# 2_HV_MUX.net
KiCad netlist of a schematic drawn in Altium Designer
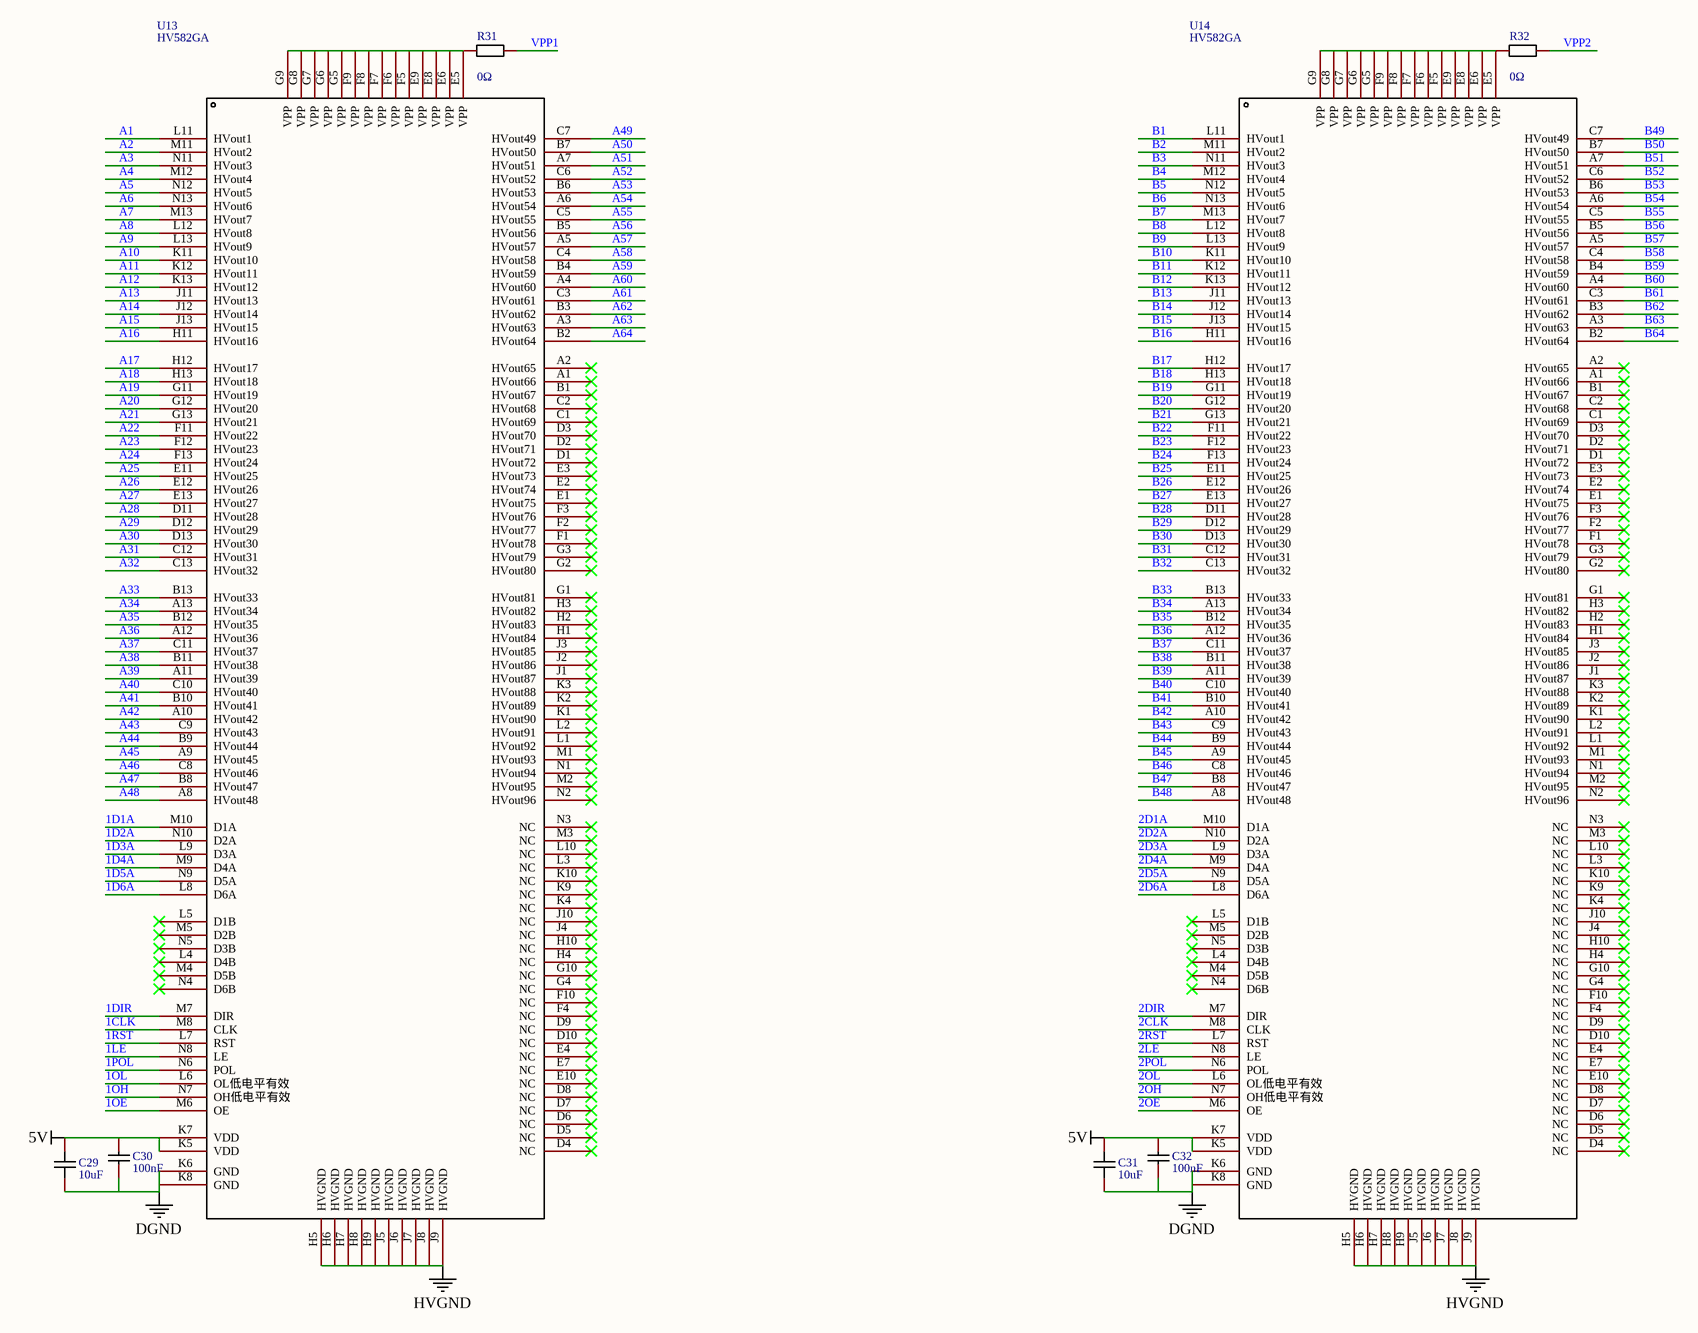
[diagram p0: 2_HV_MUX.schdoc]

(export (version "E")
  (design (tool "Eeschema 10.0.6"))
  (components
    (comp (ref "C29")
      (value "10uF")
      (fields
        (field (name "NAME") "10uF")
        (field (name "MANUFACTURER") "Samsung Electro-Mechanics")
        (field (name "MANUFACTURER PART") "CL05A106MP5NUNC")
      )
      (libsource (lib "altium-import") (part "root_1_CL05A106MP5NUNC_"))
    )
    (comp (ref "C30")
      (value "100nF")
      (fields
        (field (name "NAME") "100nF")
        (field (name "MANUFACTURER PART") "CL05B104KO5NNNC")
        (field (name "MANUFACTURER") "SAMSUNG")
      )
      (libsource (lib "altium-import") (part "root_1_CL05B104KO5NNNC_"))
    )
    (comp (ref "C31")
      (value "10uF")
      (fields
        (field (name "NAME") "10uF")
        (field (name "MANUFACTURER") "Samsung Electro-Mechanics")
        (field (name "MANUFACTURER PART") "CL05A106MP5NUNC")
      )
      (libsource (lib "altium-import") (part "root_1_CL05A106MP5NUNC_"))
    )
    (comp (ref "C32")
      (value "100nF")
      (fields
        (field (name "NAME") "100nF")
        (field (name "MANUFACTURER PART") "CL05B104KO5NNNC")
        (field (name "MANUFACTURER") "SAMSUNG")
      )
      (libsource (lib "altium-import") (part "root_1_CL05B104KO5NNNC_"))
    )
    (comp (ref "R31")
      (value "0Ω")
      (description "电阻类型:厚膜电阻;阻值:0Ω;精度:±1%;功率:250mW;温度系数:±800ppm/℃;最大工作电压:200V;工作温度范围:-55℃~+155℃;")
      (fields
        (field (name "MANUFACTURER") "UNI-ROYAL(厚声)")
        (field (name "MANUFACTURER PART") "1206W4F0000T5E")
      )
      (libsource (lib "altium-import") (part "root_0_1206W4F0000T5E_"))
    )
    (comp (ref "R32")
      (value "0Ω")
      (description "电阻类型:厚膜电阻;阻值:0Ω;精度:±1%;功率:250mW;温度系数:±800ppm/℃;最大工作电压:200V;工作温度范围:-55℃~+155℃;")
      (fields
        (field (name "MANUFACTURER") "UNI-ROYAL(厚声)")
        (field (name "MANUFACTURER PART") "1206W4F0000T5E")
      )
      (libsource (lib "altium-import") (part "root_0_1206W4F0000T5E_"))
    )
    (comp (ref "U13")
      (value "HV582GA")
      (fields (field (name "NAME") "HV582GA") (field (name "MANUFACTURER") "Microchip"))
      (libsource (lib "altium-import") (part "root_0_HV582GA_"))
    )
    (comp (ref "U14")
      (value "HV582GA")
      (fields (field (name "NAME") "HV582GA") (field (name "MANUFACTURER") "Microchip"))
      (libsource (lib "altium-import") (part "root_0_HV582GA_"))
    )
  )
  (nets
    (net (code "1") (name "/1CLK") (class "Default")
      (node (ref "U13") (pin "M8") (pinfunction "CLK_M8") (pintype "passive"))
    )
    (net (code "2") (name "/1D1A") (class "Default")
      (node (ref "U13") (pin "M10") (pinfunction "D1A_M10") (pintype "passive"))
    )
    (net (code "3") (name "/1D2A") (class "Default")
      (node (ref "U13") (pin "N10") (pinfunction "D2A_N10") (pintype "passive"))
    )
    (net (code "4") (name "/1D3A") (class "Default")
      (node (ref "U13") (pin "L9") (pinfunction "D3A_L9") (pintype "passive"))
    )
    (net (code "5") (name "/1D4A") (class "Default")
      (node (ref "U13") (pin "M9") (pinfunction "D4A_M9") (pintype "passive"))
    )
    (net (code "6") (name "/1D5A") (class "Default")
      (node (ref "U13") (pin "N9") (pinfunction "D5A_N9") (pintype "passive"))
    )
    (net (code "7") (name "/1D6A") (class "Default")
      (node (ref "U13") (pin "L8") (pinfunction "D6A_L8") (pintype "passive"))
    )
    (net (code "8") (name "/1DIR") (class "Default")
      (node (ref "U13") (pin "M7") (pinfunction "DIR_M7") (pintype "passive"))
    )
    (net (code "9") (name "/1LE") (class "Default")
      (node (ref "U13") (pin "N8") (pinfunction "LE_N8") (pintype "passive"))
    )
    (net (code "10") (name "/1OE") (class "Default")
      (node (ref "U13") (pin "M6") (pinfunction "OE_M6") (pintype "passive"))
    )
    (net (code "11") (name "/1OH") (class "Default")
      (node (ref "U13") (pin "N7") (pinfunction "OH低电平有效_N7") (pintype "passive"))
    )
    (net (code "12") (name "/1OL") (class "Default")
      (node (ref "U13") (pin "L6") (pinfunction "OL低电平有效_L6") (pintype "passive"))
    )
    (net (code "13") (name "/1POL") (class "Default")
      (node (ref "U13") (pin "N6") (pinfunction "POL_N6") (pintype "passive"))
    )
    (net (code "14") (name "/1RST") (class "Default")
      (node (ref "U13") (pin "L7") (pinfunction "RST_L7") (pintype "passive"))
    )
    (net (code "15") (name "/2CLK") (class "Default")
      (node (ref "U14") (pin "M8") (pinfunction "CLK_M8") (pintype "passive"))
    )
    (net (code "16") (name "/2D1A") (class "Default")
      (node (ref "U14") (pin "M10") (pinfunction "D1A_M10") (pintype "passive"))
    )
    (net (code "17") (name "/2D2A") (class "Default")
      (node (ref "U14") (pin "N10") (pinfunction "D2A_N10") (pintype "passive"))
    )
    (net (code "18") (name "/2D3A") (class "Default")
      (node (ref "U14") (pin "L9") (pinfunction "D3A_L9") (pintype "passive"))
    )
    (net (code "19") (name "/2D4A") (class "Default")
      (node (ref "U14") (pin "M9") (pinfunction "D4A_M9") (pintype "passive"))
    )
    (net (code "20") (name "/2D5A") (class "Default")
      (node (ref "U14") (pin "N9") (pinfunction "D5A_N9") (pintype "passive"))
    )
    (net (code "21") (name "/2D6A") (class "Default")
      (node (ref "U14") (pin "L8") (pinfunction "D6A_L8") (pintype "passive"))
    )
    (net (code "22") (name "/2DIR") (class "Default")
      (node (ref "U14") (pin "M7") (pinfunction "DIR_M7") (pintype "passive"))
    )
    (net (code "23") (name "/2LE") (class "Default")
      (node (ref "U14") (pin "N8") (pinfunction "LE_N8") (pintype "passive"))
    )
    (net (code "24") (name "/2OE") (class "Default")
      (node (ref "U14") (pin "M6") (pinfunction "OE_M6") (pintype "passive"))
    )
    (net (code "25") (name "/2OH") (class "Default")
      (node (ref "U14") (pin "N7") (pinfunction "OH低电平有效_N7") (pintype "passive"))
    )
    (net (code "26") (name "/2OL") (class "Default")
      (node (ref "U14") (pin "L6") (pinfunction "OL低电平有效_L6") (pintype "passive"))
    )
    (net (code "27") (name "/2POL") (class "Default")
      (node (ref "U14") (pin "N6") (pinfunction "POL_N6") (pintype "passive"))
    )
    (net (code "28") (name "/2RST") (class "Default")
      (node (ref "U14") (pin "L7") (pinfunction "RST_L7") (pintype "passive"))
    )
    (net (code "29") (name "/A1") (class "Default")
      (node (ref "U13") (pin "L11") (pinfunction "HVout1_L11") (pintype "passive"))
    )
    (net (code "30") (name "/A2") (class "Default")
      (node (ref "U13") (pin "M11") (pinfunction "HVout2_M11") (pintype "passive"))
    )
    (net (code "31") (name "/A3") (class "Default")
      (node (ref "U13") (pin "N11") (pinfunction "HVout3_N11") (pintype "passive"))
    )
    (net (code "32") (name "/A4") (class "Default")
      (node (ref "U13") (pin "M12") (pinfunction "HVout4_M12") (pintype "passive"))
    )
    (net (code "33") (name "/A5") (class "Default")
      (node (ref "U13") (pin "N12") (pinfunction "HVout5_N12") (pintype "passive"))
    )
    (net (code "34") (name "/A6") (class "Default")
      (node (ref "U13") (pin "N13") (pinfunction "HVout6_N13") (pintype "passive"))
    )
    (net (code "35") (name "/A7") (class "Default")
      (node (ref "U13") (pin "M13") (pinfunction "HVout7_M13") (pintype "passive"))
    )
    (net (code "36") (name "/A8") (class "Default")
      (node (ref "U13") (pin "L12") (pinfunction "HVout8_L12") (pintype "passive"))
    )
    (net (code "37") (name "/A9") (class "Default")
      (node (ref "U13") (pin "L13") (pinfunction "HVout9_L13") (pintype "passive"))
    )
    (net (code "38") (name "/A10") (class "Default")
      (node (ref "U13") (pin "K11") (pinfunction "HVout10_K11") (pintype "passive"))
    )
    (net (code "39") (name "/A11") (class "Default")
      (node (ref "U13") (pin "K12") (pinfunction "HVout11_K12") (pintype "passive"))
    )
    (net (code "40") (name "/A12") (class "Default")
      (node (ref "U13") (pin "K13") (pinfunction "HVout12_K13") (pintype "passive"))
    )
    (net (code "41") (name "/A13") (class "Default")
      (node (ref "U13") (pin "J11") (pinfunction "HVout13_J11") (pintype "passive"))
    )
    (net (code "42") (name "/A14") (class "Default")
      (node (ref "U13") (pin "J12") (pinfunction "HVout14_J12") (pintype "passive"))
    )
    (net (code "43") (name "/A15") (class "Default")
      (node (ref "U13") (pin "J13") (pinfunction "HVout15_J13") (pintype "passive"))
    )
    (net (code "44") (name "/A16") (class "Default")
      (node (ref "U13") (pin "H11") (pinfunction "HVout16_H11") (pintype "passive"))
    )
    (net (code "45") (name "/A17") (class "Default")
      (node (ref "U13") (pin "H12") (pinfunction "HVout17_H12") (pintype "passive"))
    )
    (net (code "46") (name "/A18") (class "Default")
      (node (ref "U13") (pin "H13") (pinfunction "HVout18_H13") (pintype "passive"))
    )
    (net (code "47") (name "/A19") (class "Default")
      (node (ref "U13") (pin "G11") (pinfunction "HVout19_G11") (pintype "passive"))
    )
    (net (code "48") (name "/A20") (class "Default")
      (node (ref "U13") (pin "G12") (pinfunction "HVout20_G12") (pintype "passive"))
    )
    (net (code "49") (name "/A21") (class "Default")
      (node (ref "U13") (pin "G13") (pinfunction "HVout21_G13") (pintype "passive"))
    )
    (net (code "50") (name "/A22") (class "Default")
      (node (ref "U13") (pin "F11") (pinfunction "HVout22_F11") (pintype "passive"))
    )
    (net (code "51") (name "/A23") (class "Default")
      (node (ref "U13") (pin "F12") (pinfunction "HVout23_F12") (pintype "passive"))
    )
    (net (code "52") (name "/A24") (class "Default")
      (node (ref "U13") (pin "F13") (pinfunction "HVout24_F13") (pintype "passive"))
    )
    (net (code "53") (name "/A25") (class "Default")
      (node (ref "U13") (pin "E11") (pinfunction "HVout25_E11") (pintype "passive"))
    )
    (net (code "54") (name "/A26") (class "Default")
      (node (ref "U13") (pin "E12") (pinfunction "HVout26_E12") (pintype "passive"))
    )
    (net (code "55") (name "/A27") (class "Default")
      (node (ref "U13") (pin "E13") (pinfunction "HVout27_E13") (pintype "passive"))
    )
    (net (code "56") (name "/A28") (class "Default")
      (node (ref "U13") (pin "D11") (pinfunction "HVout28_D11") (pintype "passive"))
    )
    (net (code "57") (name "/A29") (class "Default")
      (node (ref "U13") (pin "D12") (pinfunction "HVout29_D12") (pintype "passive"))
    )
    (net (code "58") (name "/A30") (class "Default")
      (node (ref "U13") (pin "D13") (pinfunction "HVout30_D13") (pintype "passive"))
    )
    (net (code "59") (name "/A31") (class "Default")
      (node (ref "U13") (pin "C12") (pinfunction "HVout31_C12") (pintype "passive"))
    )
    (net (code "60") (name "/A32") (class "Default")
      (node (ref "U13") (pin "C13") (pinfunction "HVout32_C13") (pintype "passive"))
    )
    (net (code "61") (name "/A33") (class "Default")
      (node (ref "U13") (pin "B13") (pinfunction "HVout33_B13") (pintype "passive"))
    )
    (net (code "62") (name "/A34") (class "Default")
      (node (ref "U13") (pin "A13") (pinfunction "HVout34_A13") (pintype "passive"))
    )
    (net (code "63") (name "/A35") (class "Default")
      (node (ref "U13") (pin "B12") (pinfunction "HVout35_B12") (pintype "passive"))
    )
    (net (code "64") (name "/A36") (class "Default")
      (node (ref "U13") (pin "A12") (pinfunction "HVout36_A12") (pintype "passive"))
    )
    (net (code "65") (name "/A37") (class "Default")
      (node (ref "U13") (pin "C11") (pinfunction "HVout37_C11") (pintype "passive"))
    )
    (net (code "66") (name "/A38") (class "Default")
      (node (ref "U13") (pin "B11") (pinfunction "HVout38_B11") (pintype "passive"))
    )
    (net (code "67") (name "/A39") (class "Default")
      (node (ref "U13") (pin "A11") (pinfunction "HVout39_A11") (pintype "passive"))
    )
    (net (code "68") (name "/A40") (class "Default")
      (node (ref "U13") (pin "C10") (pinfunction "HVout40_C10") (pintype "passive"))
    )
    (net (code "69") (name "/A41") (class "Default")
      (node (ref "U13") (pin "B10") (pinfunction "HVout41_B10") (pintype "passive"))
    )
    (net (code "70") (name "/A42") (class "Default")
      (node (ref "U13") (pin "A10") (pinfunction "HVout42_A10") (pintype "passive"))
    )
    (net (code "71") (name "/A43") (class "Default")
      (node (ref "U13") (pin "C9") (pinfunction "HVout43_C9") (pintype "passive"))
    )
    (net (code "72") (name "/A44") (class "Default")
      (node (ref "U13") (pin "B9") (pinfunction "HVout44_B9") (pintype "passive"))
    )
    (net (code "73") (name "/A45") (class "Default")
      (node (ref "U13") (pin "A9") (pinfunction "HVout45_A9") (pintype "passive"))
    )
    (net (code "74") (name "/A46") (class "Default")
      (node (ref "U13") (pin "C8") (pinfunction "HVout46_C8") (pintype "passive"))
    )
    (net (code "75") (name "/A47") (class "Default")
      (node (ref "U13") (pin "B8") (pinfunction "HVout47_B8") (pintype "passive"))
    )
    (net (code "76") (name "/A48") (class "Default")
      (node (ref "U13") (pin "A8") (pinfunction "HVout48_A8") (pintype "passive"))
    )
    (net (code "77") (name "/A49") (class "Default")
      (node (ref "U13") (pin "C7") (pinfunction "HVout49_C7") (pintype "passive"))
    )
    (net (code "78") (name "/A50") (class "Default")
      (node (ref "U13") (pin "B7") (pinfunction "HVout50_B7") (pintype "passive"))
    )
    (net (code "79") (name "/A51") (class "Default")
      (node (ref "U13") (pin "A7") (pinfunction "HVout51_A7") (pintype "passive"))
    )
    (net (code "80") (name "/A52") (class "Default")
      (node (ref "U13") (pin "C6") (pinfunction "HVout52_C6") (pintype "passive"))
    )
    (net (code "81") (name "/A53") (class "Default")
      (node (ref "U13") (pin "B6") (pinfunction "HVout53_B6") (pintype "passive"))
    )
    (net (code "82") (name "/A54") (class "Default")
      (node (ref "U13") (pin "A6") (pinfunction "HVout54_A6") (pintype "passive"))
    )
    (net (code "83") (name "/A55") (class "Default")
      (node (ref "U13") (pin "C5") (pinfunction "HVout55_C5") (pintype "passive"))
    )
    (net (code "84") (name "/A56") (class "Default")
      (node (ref "U13") (pin "B5") (pinfunction "HVout56_B5") (pintype "passive"))
    )
    (net (code "85") (name "/A57") (class "Default")
      (node (ref "U13") (pin "A5") (pinfunction "HVout57_A5") (pintype "passive"))
    )
    (net (code "86") (name "/A58") (class "Default")
      (node (ref "U13") (pin "C4") (pinfunction "HVout58_C4") (pintype "passive"))
    )
    (net (code "87") (name "/A59") (class "Default")
      (node (ref "U13") (pin "B4") (pinfunction "HVout59_B4") (pintype "passive"))
    )
    (net (code "88") (name "/A60") (class "Default")
      (node (ref "U13") (pin "A4") (pinfunction "HVout60_A4") (pintype "passive"))
    )
    (net (code "89") (name "/A61") (class "Default")
      (node (ref "U13") (pin "C3") (pinfunction "HVout61_C3") (pintype "passive"))
    )
    (net (code "90") (name "/A62") (class "Default")
      (node (ref "U13") (pin "B3") (pinfunction "HVout62_B3") (pintype "passive"))
    )
    (net (code "91") (name "/A63") (class "Default")
      (node (ref "U13") (pin "A3") (pinfunction "HVout63_A3") (pintype "passive"))
    )
    (net (code "92") (name "/A64") (class "Default")
      (node (ref "U13") (pin "B2") (pinfunction "HVout64_B2") (pintype "passive"))
    )
    (net (code "93") (name "/B1") (class "Default")
      (node (ref "U14") (pin "L11") (pinfunction "HVout1_L11") (pintype "passive"))
    )
    (net (code "94") (name "/B2") (class "Default")
      (node (ref "U14") (pin "M11") (pinfunction "HVout2_M11") (pintype "passive"))
    )
    (net (code "95") (name "/B3") (class "Default")
      (node (ref "U14") (pin "N11") (pinfunction "HVout3_N11") (pintype "passive"))
    )
    (net (code "96") (name "/B4") (class "Default")
      (node (ref "U14") (pin "M12") (pinfunction "HVout4_M12") (pintype "passive"))
    )
    (net (code "97") (name "/B5") (class "Default")
      (node (ref "U14") (pin "N12") (pinfunction "HVout5_N12") (pintype "passive"))
    )
    (net (code "98") (name "/B6") (class "Default")
      (node (ref "U14") (pin "N13") (pinfunction "HVout6_N13") (pintype "passive"))
    )
    (net (code "99") (name "/B7") (class "Default")
      (node (ref "U14") (pin "M13") (pinfunction "HVout7_M13") (pintype "passive"))
    )
    (net (code "100") (name "/B8") (class "Default")
      (node (ref "U14") (pin "L12") (pinfunction "HVout8_L12") (pintype "passive"))
    )
    (net (code "101") (name "/B9") (class "Default")
      (node (ref "U14") (pin "L13") (pinfunction "HVout9_L13") (pintype "passive"))
    )
    (net (code "102") (name "/B10") (class "Default")
      (node (ref "U14") (pin "K11") (pinfunction "HVout10_K11") (pintype "passive"))
    )
    (net (code "103") (name "/B11") (class "Default")
      (node (ref "U14") (pin "K12") (pinfunction "HVout11_K12") (pintype "passive"))
    )
    (net (code "104") (name "/B12") (class "Default")
      (node (ref "U14") (pin "K13") (pinfunction "HVout12_K13") (pintype "passive"))
    )
    (net (code "105") (name "/B13") (class "Default")
      (node (ref "U14") (pin "J11") (pinfunction "HVout13_J11") (pintype "passive"))
    )
    (net (code "106") (name "/B14") (class "Default")
      (node (ref "U14") (pin "J12") (pinfunction "HVout14_J12") (pintype "passive"))
    )
    (net (code "107") (name "/B15") (class "Default")
      (node (ref "U14") (pin "J13") (pinfunction "HVout15_J13") (pintype "passive"))
    )
    (net (code "108") (name "/B16") (class "Default")
      (node (ref "U14") (pin "H11") (pinfunction "HVout16_H11") (pintype "passive"))
    )
    (net (code "109") (name "/B17") (class "Default")
      (node (ref "U14") (pin "H12") (pinfunction "HVout17_H12") (pintype "passive"))
    )
    (net (code "110") (name "/B18") (class "Default")
      (node (ref "U14") (pin "H13") (pinfunction "HVout18_H13") (pintype "passive"))
    )
    (net (code "111") (name "/B19") (class "Default")
      (node (ref "U14") (pin "G11") (pinfunction "HVout19_G11") (pintype "passive"))
    )
    (net (code "112") (name "/B20") (class "Default")
      (node (ref "U14") (pin "G12") (pinfunction "HVout20_G12") (pintype "passive"))
    )
    (net (code "113") (name "/B21") (class "Default")
      (node (ref "U14") (pin "G13") (pinfunction "HVout21_G13") (pintype "passive"))
    )
    (net (code "114") (name "/B22") (class "Default")
      (node (ref "U14") (pin "F11") (pinfunction "HVout22_F11") (pintype "passive"))
    )
    (net (code "115") (name "/B23") (class "Default")
      (node (ref "U14") (pin "F12") (pinfunction "HVout23_F12") (pintype "passive"))
    )
    (net (code "116") (name "/B24") (class "Default")
      (node (ref "U14") (pin "F13") (pinfunction "HVout24_F13") (pintype "passive"))
    )
    (net (code "117") (name "/B25") (class "Default")
      (node (ref "U14") (pin "E11") (pinfunction "HVout25_E11") (pintype "passive"))
    )
    (net (code "118") (name "/B26") (class "Default")
      (node (ref "U14") (pin "E12") (pinfunction "HVout26_E12") (pintype "passive"))
    )
    (net (code "119") (name "/B27") (class "Default")
      (node (ref "U14") (pin "E13") (pinfunction "HVout27_E13") (pintype "passive"))
    )
    (net (code "120") (name "/B28") (class "Default")
      (node (ref "U14") (pin "D11") (pinfunction "HVout28_D11") (pintype "passive"))
    )
    (net (code "121") (name "/B29") (class "Default")
      (node (ref "U14") (pin "D12") (pinfunction "HVout29_D12") (pintype "passive"))
    )
    (net (code "122") (name "/B30") (class "Default")
      (node (ref "U14") (pin "D13") (pinfunction "HVout30_D13") (pintype "passive"))
    )
    (net (code "123") (name "/B31") (class "Default")
      (node (ref "U14") (pin "C12") (pinfunction "HVout31_C12") (pintype "passive"))
    )
    (net (code "124") (name "/B32") (class "Default")
      (node (ref "U14") (pin "C13") (pinfunction "HVout32_C13") (pintype "passive"))
    )
    (net (code "125") (name "/B33") (class "Default")
      (node (ref "U14") (pin "B13") (pinfunction "HVout33_B13") (pintype "passive"))
    )
    (net (code "126") (name "/B34") (class "Default")
      (node (ref "U14") (pin "A13") (pinfunction "HVout34_A13") (pintype "passive"))
    )
    (net (code "127") (name "/B35") (class "Default")
      (node (ref "U14") (pin "B12") (pinfunction "HVout35_B12") (pintype "passive"))
    )
    (net (code "128") (name "/B36") (class "Default")
      (node (ref "U14") (pin "A12") (pinfunction "HVout36_A12") (pintype "passive"))
    )
    (net (code "129") (name "/B37") (class "Default")
      (node (ref "U14") (pin "C11") (pinfunction "HVout37_C11") (pintype "passive"))
    )
    (net (code "130") (name "/B38") (class "Default")
      (node (ref "U14") (pin "B11") (pinfunction "HVout38_B11") (pintype "passive"))
    )
    (net (code "131") (name "/B39") (class "Default")
      (node (ref "U14") (pin "A11") (pinfunction "HVout39_A11") (pintype "passive"))
    )
    (net (code "132") (name "/B40") (class "Default")
      (node (ref "U14") (pin "C10") (pinfunction "HVout40_C10") (pintype "passive"))
    )
    (net (code "133") (name "/B41") (class "Default")
      (node (ref "U14") (pin "B10") (pinfunction "HVout41_B10") (pintype "passive"))
    )
    (net (code "134") (name "/B42") (class "Default")
      (node (ref "U14") (pin "A10") (pinfunction "HVout42_A10") (pintype "passive"))
    )
    (net (code "135") (name "/B43") (class "Default")
      (node (ref "U14") (pin "C9") (pinfunction "HVout43_C9") (pintype "passive"))
    )
    (net (code "136") (name "/B44") (class "Default")
      (node (ref "U14") (pin "B9") (pinfunction "HVout44_B9") (pintype "passive"))
    )
    (net (code "137") (name "/B45") (class "Default")
      (node (ref "U14") (pin "A9") (pinfunction "HVout45_A9") (pintype "passive"))
    )
    (net (code "138") (name "/B46") (class "Default")
      (node (ref "U14") (pin "C8") (pinfunction "HVout46_C8") (pintype "passive"))
    )
    (net (code "139") (name "/B47") (class "Default")
      (node (ref "U14") (pin "B8") (pinfunction "HVout47_B8") (pintype "passive"))
    )
    (net (code "140") (name "/B48") (class "Default")
      (node (ref "U14") (pin "A8") (pinfunction "HVout48_A8") (pintype "passive"))
    )
    (net (code "141") (name "/B49") (class "Default")
      (node (ref "U14") (pin "C7") (pinfunction "HVout49_C7") (pintype "passive"))
    )
    (net (code "142") (name "/B50") (class "Default")
      (node (ref "U14") (pin "B7") (pinfunction "HVout50_B7") (pintype "passive"))
    )
    (net (code "143") (name "/B51") (class "Default")
      (node (ref "U14") (pin "A7") (pinfunction "HVout51_A7") (pintype "passive"))
    )
    (net (code "144") (name "/B52") (class "Default")
      (node (ref "U14") (pin "C6") (pinfunction "HVout52_C6") (pintype "passive"))
    )
    (net (code "145") (name "/B53") (class "Default")
      (node (ref "U14") (pin "B6") (pinfunction "HVout53_B6") (pintype "passive"))
    )
    (net (code "146") (name "/B54") (class "Default")
      (node (ref "U14") (pin "A6") (pinfunction "HVout54_A6") (pintype "passive"))
    )
    (net (code "147") (name "/B55") (class "Default")
      (node (ref "U14") (pin "C5") (pinfunction "HVout55_C5") (pintype "passive"))
    )
    (net (code "148") (name "/B56") (class "Default")
      (node (ref "U14") (pin "B5") (pinfunction "HVout56_B5") (pintype "passive"))
    )
    (net (code "149") (name "/B57") (class "Default")
      (node (ref "U14") (pin "A5") (pinfunction "HVout57_A5") (pintype "passive"))
    )
    (net (code "150") (name "/B58") (class "Default")
      (node (ref "U14") (pin "C4") (pinfunction "HVout58_C4") (pintype "passive"))
    )
    (net (code "151") (name "/B59") (class "Default")
      (node (ref "U14") (pin "B4") (pinfunction "HVout59_B4") (pintype "passive"))
    )
    (net (code "152") (name "/B60") (class "Default")
      (node (ref "U14") (pin "A4") (pinfunction "HVout60_A4") (pintype "passive"))
    )
    (net (code "153") (name "/B61") (class "Default")
      (node (ref "U14") (pin "C3") (pinfunction "HVout61_C3") (pintype "passive"))
    )
    (net (code "154") (name "/B62") (class "Default")
      (node (ref "U14") (pin "B3") (pinfunction "HVout62_B3") (pintype "passive"))
    )
    (net (code "155") (name "/B63") (class "Default")
      (node (ref "U14") (pin "A3") (pinfunction "HVout63_A3") (pintype "passive"))
    )
    (net (code "156") (name "/B64") (class "Default")
      (node (ref "U14") (pin "B2") (pinfunction "HVout64_B2") (pintype "passive"))
    )
    (net (code "157") (name "/VPP1") (class "Default")
      (node (ref "R31") (pin "2") (pinfunction "2_2") (pintype "passive"))
    )
    (net (code "158") (name "/VPP2") (class "Default")
      (node (ref "R32") (pin "2") (pinfunction "2_2") (pintype "passive"))
    )
    (net (code "159") (name "5V") (class "Default")
      (node (ref "C29") (pin "2") (pinfunction "2_2") (pintype "passive"))
      (node (ref "C30") (pin "2") (pinfunction "2_2") (pintype "passive"))
      (node (ref "C31") (pin "2") (pinfunction "2_2") (pintype "passive"))
      (node (ref "C32") (pin "2") (pinfunction "2_2") (pintype "passive"))
      (node (ref "U13") (pin "K5") (pinfunction "VDD_K5") (pintype "passive"))
      (node (ref "U13") (pin "K7") (pinfunction "VDD_K7") (pintype "passive"))
      (node (ref "U14") (pin "K5") (pinfunction "VDD_K5") (pintype "passive"))
      (node (ref "U14") (pin "K7") (pinfunction "VDD_K7") (pintype "passive"))
    )
    (net (code "160") (name "DGND") (class "Default")
      (node (ref "C29") (pin "1") (pinfunction "1_1") (pintype "passive"))
      (node (ref "C30") (pin "1") (pinfunction "1_1") (pintype "passive"))
      (node (ref "C31") (pin "1") (pinfunction "1_1") (pintype "passive"))
      (node (ref "C32") (pin "1") (pinfunction "1_1") (pintype "passive"))
      (node (ref "U13") (pin "K6") (pinfunction "GND_K6") (pintype "passive"))
      (node (ref "U13") (pin "K8") (pinfunction "GND_K8") (pintype "passive"))
      (node (ref "U14") (pin "K6") (pinfunction "GND_K6") (pintype "passive"))
      (node (ref "U14") (pin "K8") (pinfunction "GND_K8") (pintype "passive"))
    )
    (net (code "161") (name "HVGND") (class "Default")
      (node (ref "U13") (pin "H5") (pinfunction "HVGND_H5") (pintype "passive"))
      (node (ref "U13") (pin "H6") (pinfunction "HVGND_H6") (pintype "passive"))
      (node (ref "U13") (pin "H7") (pinfunction "HVGND_H7") (pintype "passive"))
      (node (ref "U13") (pin "H8") (pinfunction "HVGND_H8") (pintype "passive"))
      (node (ref "U13") (pin "H9") (pinfunction "HVGND_H9") (pintype "passive"))
      (node (ref "U13") (pin "J5") (pinfunction "HVGND_J5") (pintype "passive"))
      (node (ref "U13") (pin "J6") (pinfunction "HVGND_J6") (pintype "passive"))
      (node (ref "U13") (pin "J7") (pinfunction "HVGND_J7") (pintype "passive"))
      (node (ref "U13") (pin "J8") (pinfunction "HVGND_J8") (pintype "passive"))
      (node (ref "U13") (pin "J9") (pinfunction "HVGND_J9") (pintype "passive"))
      (node (ref "U14") (pin "H5") (pinfunction "HVGND_H5") (pintype "passive"))
      (node (ref "U14") (pin "H6") (pinfunction "HVGND_H6") (pintype "passive"))
      (node (ref "U14") (pin "H7") (pinfunction "HVGND_H7") (pintype "passive"))
      (node (ref "U14") (pin "H8") (pinfunction "HVGND_H8") (pintype "passive"))
      (node (ref "U14") (pin "H9") (pinfunction "HVGND_H9") (pintype "passive"))
      (node (ref "U14") (pin "J5") (pinfunction "HVGND_J5") (pintype "passive"))
      (node (ref "U14") (pin "J6") (pinfunction "HVGND_J6") (pintype "passive"))
      (node (ref "U14") (pin "J7") (pinfunction "HVGND_J7") (pintype "passive"))
      (node (ref "U14") (pin "J8") (pinfunction "HVGND_J8") (pintype "passive"))
      (node (ref "U14") (pin "J9") (pinfunction "HVGND_J9") (pintype "passive"))
    )
    (net (code "162") (name "Net-(R31-Pad1)") (class "Default")
      (node (ref "R31") (pin "1") (pinfunction "1_1") (pintype "passive"))
      (node (ref "U13") (pin "E5") (pinfunction "VPP_E5") (pintype "passive"))
      (node (ref "U13") (pin "E6") (pinfunction "VPP_E6") (pintype "passive"))
      (node (ref "U13") (pin "E8") (pinfunction "VPP_E8") (pintype "passive"))
      (node (ref "U13") (pin "E9") (pinfunction "VPP_E9") (pintype "passive"))
      (node (ref "U13") (pin "F5") (pinfunction "VPP_F5") (pintype "passive"))
      (node (ref "U13") (pin "F6") (pinfunction "VPP_F6") (pintype "passive"))
      (node (ref "U13") (pin "F7") (pinfunction "VPP_F7") (pintype "passive"))
      (node (ref "U13") (pin "F8") (pinfunction "VPP_F8") (pintype "passive"))
      (node (ref "U13") (pin "F9") (pinfunction "VPP_F9") (pintype "passive"))
      (node (ref "U13") (pin "G5") (pinfunction "VPP_G5") (pintype "passive"))
      (node (ref "U13") (pin "G6") (pinfunction "VPP_G6") (pintype "passive"))
      (node (ref "U13") (pin "G7") (pinfunction "VPP_G7") (pintype "passive"))
      (node (ref "U13") (pin "G8") (pinfunction "VPP_G8") (pintype "passive"))
      (node (ref "U13") (pin "G9") (pinfunction "VPP_G9") (pintype "passive"))
    )
    (net (code "163") (name "Net-(R32-Pad1)") (class "Default")
      (node (ref "R32") (pin "1") (pinfunction "1_1") (pintype "passive"))
      (node (ref "U14") (pin "E5") (pinfunction "VPP_E5") (pintype "passive"))
      (node (ref "U14") (pin "E6") (pinfunction "VPP_E6") (pintype "passive"))
      (node (ref "U14") (pin "E8") (pinfunction "VPP_E8") (pintype "passive"))
      (node (ref "U14") (pin "E9") (pinfunction "VPP_E9") (pintype "passive"))
      (node (ref "U14") (pin "F5") (pinfunction "VPP_F5") (pintype "passive"))
      (node (ref "U14") (pin "F6") (pinfunction "VPP_F6") (pintype "passive"))
      (node (ref "U14") (pin "F7") (pinfunction "VPP_F7") (pintype "passive"))
      (node (ref "U14") (pin "F8") (pinfunction "VPP_F8") (pintype "passive"))
      (node (ref "U14") (pin "F9") (pinfunction "VPP_F9") (pintype "passive"))
      (node (ref "U14") (pin "G5") (pinfunction "VPP_G5") (pintype "passive"))
      (node (ref "U14") (pin "G6") (pinfunction "VPP_G6") (pintype "passive"))
      (node (ref "U14") (pin "G7") (pinfunction "VPP_G7") (pintype "passive"))
      (node (ref "U14") (pin "G8") (pinfunction "VPP_G8") (pintype "passive"))
      (node (ref "U14") (pin "G9") (pinfunction "VPP_G9") (pintype "passive"))
    )
    (net (code "164") (name "unconnected-(U13-D1B-PadL5)") (class "Default")
      (node (ref "U13") (pin "L5") (pinfunction "D1B_L5") (pintype "passive+no_connect"))
    )
    (net (code "165") (name "unconnected-(U13-D2B-PadM5)") (class "Default")
      (node (ref "U13") (pin "M5") (pinfunction "D2B_M5") (pintype "passive+no_connect"))
    )
    (net (code "166") (name "unconnected-(U13-D3B-PadN5)") (class "Default")
      (node (ref "U13") (pin "N5") (pinfunction "D3B_N5") (pintype "passive+no_connect"))
    )
    (net (code "167") (name "unconnected-(U13-D4B-PadL4)") (class "Default")
      (node (ref "U13") (pin "L4") (pinfunction "D4B_L4") (pintype "passive+no_connect"))
    )
    (net (code "168") (name "unconnected-(U13-D5B-PadM4)") (class "Default")
      (node (ref "U13") (pin "M4") (pinfunction "D5B_M4") (pintype "passive+no_connect"))
    )
    (net (code "169") (name "unconnected-(U13-D6B-PadN4)") (class "Default")
      (node (ref "U13") (pin "N4") (pinfunction "D6B_N4") (pintype "passive+no_connect"))
    )
    (net (code "170") (name "unconnected-(U13-HVout65-PadA2)") (class "Default")
      (node (ref "U13") (pin "A2") (pinfunction "HVout65_A2") (pintype "passive+no_connect"))
    )
    (net (code "171") (name "unconnected-(U13-HVout66-PadA1)") (class "Default")
      (node (ref "U13") (pin "A1") (pinfunction "HVout66_A1") (pintype "passive+no_connect"))
    )
    (net (code "172") (name "unconnected-(U13-HVout67-PadB1)") (class "Default")
      (node (ref "U13") (pin "B1") (pinfunction "HVout67_B1") (pintype "passive+no_connect"))
    )
    (net (code "173") (name "unconnected-(U13-HVout68-PadC2)") (class "Default")
      (node (ref "U13") (pin "C2") (pinfunction "HVout68_C2") (pintype "passive+no_connect"))
    )
    (net (code "174") (name "unconnected-(U13-HVout69-PadC1)") (class "Default")
      (node (ref "U13") (pin "C1") (pinfunction "HVout69_C1") (pintype "passive+no_connect"))
    )
    (net (code "175") (name "unconnected-(U13-HVout70-PadD3)") (class "Default")
      (node (ref "U13") (pin "D3") (pinfunction "HVout70_D3") (pintype "passive+no_connect"))
    )
    (net (code "176") (name "unconnected-(U13-HVout71-PadD2)") (class "Default")
      (node (ref "U13") (pin "D2") (pinfunction "HVout71_D2") (pintype "passive+no_connect"))
    )
    (net (code "177") (name "unconnected-(U13-HVout72-PadD1)") (class "Default")
      (node (ref "U13") (pin "D1") (pinfunction "HVout72_D1") (pintype "passive+no_connect"))
    )
    (net (code "178") (name "unconnected-(U13-HVout73-PadE3)") (class "Default")
      (node (ref "U13") (pin "E3") (pinfunction "HVout73_E3") (pintype "passive+no_connect"))
    )
    (net (code "179") (name "unconnected-(U13-HVout74-PadE2)") (class "Default")
      (node (ref "U13") (pin "E2") (pinfunction "HVout74_E2") (pintype "passive+no_connect"))
    )
    (net (code "180") (name "unconnected-(U13-HVout75-PadE1)") (class "Default")
      (node (ref "U13") (pin "E1") (pinfunction "HVout75_E1") (pintype "passive+no_connect"))
    )
    (net (code "181") (name "unconnected-(U13-HVout76-PadF3)") (class "Default")
      (node (ref "U13") (pin "F3") (pinfunction "HVout76_F3") (pintype "passive+no_connect"))
    )
    (net (code "182") (name "unconnected-(U13-HVout77-PadF2)") (class "Default")
      (node (ref "U13") (pin "F2") (pinfunction "HVout77_F2") (pintype "passive+no_connect"))
    )
    (net (code "183") (name "unconnected-(U13-HVout78-PadF1)") (class "Default")
      (node (ref "U13") (pin "F1") (pinfunction "HVout78_F1") (pintype "passive+no_connect"))
    )
    (net (code "184") (name "unconnected-(U13-HVout79-PadG3)") (class "Default")
      (node (ref "U13") (pin "G3") (pinfunction "HVout79_G3") (pintype "passive+no_connect"))
    )
    (net (code "185") (name "unconnected-(U13-HVout80-PadG2)") (class "Default")
      (node (ref "U13") (pin "G2") (pinfunction "HVout80_G2") (pintype "passive+no_connect"))
    )
    (net (code "186") (name "unconnected-(U13-HVout81-PadG1)") (class "Default")
      (node (ref "U13") (pin "G1") (pinfunction "HVout81_G1") (pintype "passive+no_connect"))
    )
    (net (code "187") (name "unconnected-(U13-HVout82-PadH3)") (class "Default")
      (node (ref "U13") (pin "H3") (pinfunction "HVout82_H3") (pintype "passive+no_connect"))
    )
    (net (code "188") (name "unconnected-(U13-HVout83-PadH2)") (class "Default")
      (node (ref "U13") (pin "H2") (pinfunction "HVout83_H2") (pintype "passive+no_connect"))
    )
    (net (code "189") (name "unconnected-(U13-HVout84-PadH1)") (class "Default")
      (node (ref "U13") (pin "H1") (pinfunction "HVout84_H1") (pintype "passive+no_connect"))
    )
    (net (code "190") (name "unconnected-(U13-HVout85-PadJ3)") (class "Default")
      (node (ref "U13") (pin "J3") (pinfunction "HVout85_J3") (pintype "passive+no_connect"))
    )
    (net (code "191") (name "unconnected-(U13-HVout86-PadJ2)") (class "Default")
      (node (ref "U13") (pin "J2") (pinfunction "HVout86_J2") (pintype "passive+no_connect"))
    )
    (net (code "192") (name "unconnected-(U13-HVout87-PadJ1)") (class "Default")
      (node (ref "U13") (pin "J1") (pinfunction "HVout87_J1") (pintype "passive+no_connect"))
    )
    (net (code "193") (name "unconnected-(U13-HVout88-PadK3)") (class "Default")
      (node (ref "U13") (pin "K3") (pinfunction "HVout88_K3") (pintype "passive+no_connect"))
    )
    (net (code "194") (name "unconnected-(U13-HVout89-PadK2)") (class "Default")
      (node (ref "U13") (pin "K2") (pinfunction "HVout89_K2") (pintype "passive+no_connect"))
    )
    (net (code "195") (name "unconnected-(U13-HVout90-PadK1)") (class "Default")
      (node (ref "U13") (pin "K1") (pinfunction "HVout90_K1") (pintype "passive+no_connect"))
    )
    (net (code "196") (name "unconnected-(U13-HVout91-PadL2)") (class "Default")
      (node (ref "U13") (pin "L2") (pinfunction "HVout91_L2") (pintype "passive+no_connect"))
    )
    (net (code "197") (name "unconnected-(U13-HVout92-PadL1)") (class "Default")
      (node (ref "U13") (pin "L1") (pinfunction "HVout92_L1") (pintype "passive+no_connect"))
    )
    (net (code "198") (name "unconnected-(U13-HVout93-PadM1)") (class "Default")
      (node (ref "U13") (pin "M1") (pinfunction "HVout93_M1") (pintype "passive+no_connect"))
    )
    (net (code "199") (name "unconnected-(U13-HVout94-PadN1)") (class "Default")
      (node (ref "U13") (pin "N1") (pinfunction "HVout94_N1") (pintype "passive+no_connect"))
    )
    (net (code "200") (name "unconnected-(U13-HVout95-PadM2)") (class "Default")
      (node (ref "U13") (pin "M2") (pinfunction "HVout95_M2") (pintype "passive+no_connect"))
    )
    (net (code "201") (name "unconnected-(U13-HVout96-PadN2)") (class "Default")
      (node (ref "U13") (pin "N2") (pinfunction "HVout96_N2") (pintype "passive+no_connect"))
    )
    (net (code "202") (name "unconnected-(U13-NC-PadD4)") (class "Default")
      (node (ref "U13") (pin "D4") (pinfunction "NC_D4") (pintype "passive+no_connect"))
    )
    (net (code "203") (name "unconnected-(U13-NC-PadD5)") (class "Default")
      (node (ref "U13") (pin "D5") (pinfunction "NC_D5") (pintype "passive+no_connect"))
    )
    (net (code "204") (name "unconnected-(U13-NC-PadD6)") (class "Default")
      (node (ref "U13") (pin "D6") (pinfunction "NC_D6") (pintype "passive+no_connect"))
    )
    (net (code "205") (name "unconnected-(U13-NC-PadD7)") (class "Default")
      (node (ref "U13") (pin "D7") (pinfunction "NC_D7") (pintype "passive+no_connect"))
    )
    (net (code "206") (name "unconnected-(U13-NC-PadD8)") (class "Default")
      (node (ref "U13") (pin "D8") (pinfunction "NC_D8") (pintype "passive+no_connect"))
    )
    (net (code "207") (name "unconnected-(U13-NC-PadD9)") (class "Default")
      (node (ref "U13") (pin "D9") (pinfunction "NC_D9") (pintype "passive+no_connect"))
    )
    (net (code "208") (name "unconnected-(U13-NC-PadD10)") (class "Default")
      (node (ref "U13") (pin "D10") (pinfunction "NC_D10") (pintype "passive+no_connect"))
    )
    (net (code "209") (name "unconnected-(U13-NC-PadE4)") (class "Default")
      (node (ref "U13") (pin "E4") (pinfunction "NC_E4") (pintype "passive+no_connect"))
    )
    (net (code "210") (name "unconnected-(U13-NC-PadE7)") (class "Default")
      (node (ref "U13") (pin "E7") (pinfunction "NC_E7") (pintype "passive+no_connect"))
    )
    (net (code "211") (name "unconnected-(U13-NC-PadE10)") (class "Default")
      (node (ref "U13") (pin "E10") (pinfunction "NC_E10") (pintype "passive+no_connect"))
    )
    (net (code "212") (name "unconnected-(U13-NC-PadF4)") (class "Default")
      (node (ref "U13") (pin "F4") (pinfunction "NC_F4") (pintype "passive+no_connect"))
    )
    (net (code "213") (name "unconnected-(U13-NC-PadF10)") (class "Default")
      (node (ref "U13") (pin "F10") (pinfunction "NC_F10") (pintype "passive+no_connect"))
    )
    (net (code "214") (name "unconnected-(U13-NC-PadG4)") (class "Default")
      (node (ref "U13") (pin "G4") (pinfunction "NC_G4") (pintype "passive+no_connect"))
    )
    (net (code "215") (name "unconnected-(U13-NC-PadG10)") (class "Default")
      (node (ref "U13") (pin "G10") (pinfunction "NC_G10") (pintype "passive+no_connect"))
    )
    (net (code "216") (name "unconnected-(U13-NC-PadH4)") (class "Default")
      (node (ref "U13") (pin "H4") (pinfunction "NC_H4") (pintype "passive+no_connect"))
    )
    (net (code "217") (name "unconnected-(U13-NC-PadH10)") (class "Default")
      (node (ref "U13") (pin "H10") (pinfunction "NC_H10") (pintype "passive+no_connect"))
    )
    (net (code "218") (name "unconnected-(U13-NC-PadJ4)") (class "Default")
      (node (ref "U13") (pin "J4") (pinfunction "NC_J4") (pintype "passive+no_connect"))
    )
    (net (code "219") (name "unconnected-(U13-NC-PadJ10)") (class "Default")
      (node (ref "U13") (pin "J10") (pinfunction "NC_J10") (pintype "passive+no_connect"))
    )
    (net (code "220") (name "unconnected-(U13-NC-PadK4)") (class "Default")
      (node (ref "U13") (pin "K4") (pinfunction "NC_K4") (pintype "passive+no_connect"))
    )
    (net (code "221") (name "unconnected-(U13-NC-PadK9)") (class "Default")
      (node (ref "U13") (pin "K9") (pinfunction "NC_K9") (pintype "passive+no_connect"))
    )
    (net (code "222") (name "unconnected-(U13-NC-PadK10)") (class "Default")
      (node (ref "U13") (pin "K10") (pinfunction "NC_K10") (pintype "passive+no_connect"))
    )
    (net (code "223") (name "unconnected-(U13-NC-PadL3)") (class "Default")
      (node (ref "U13") (pin "L3") (pinfunction "NC_L3") (pintype "passive+no_connect"))
    )
    (net (code "224") (name "unconnected-(U13-NC-PadL10)") (class "Default")
      (node (ref "U13") (pin "L10") (pinfunction "NC_L10") (pintype "passive+no_connect"))
    )
    (net (code "225") (name "unconnected-(U13-NC-PadM3)") (class "Default")
      (node (ref "U13") (pin "M3") (pinfunction "NC_M3") (pintype "passive+no_connect"))
    )
    (net (code "226") (name "unconnected-(U13-NC-PadN3)") (class "Default")
      (node (ref "U13") (pin "N3") (pinfunction "NC_N3") (pintype "passive+no_connect"))
    )
    (net (code "227") (name "unconnected-(U14-D1B-PadL5)") (class "Default")
      (node (ref "U14") (pin "L5") (pinfunction "D1B_L5") (pintype "passive+no_connect"))
    )
    (net (code "228") (name "unconnected-(U14-D2B-PadM5)") (class "Default")
      (node (ref "U14") (pin "M5") (pinfunction "D2B_M5") (pintype "passive+no_connect"))
    )
    (net (code "229") (name "unconnected-(U14-D3B-PadN5)") (class "Default")
      (node (ref "U14") (pin "N5") (pinfunction "D3B_N5") (pintype "passive+no_connect"))
    )
    (net (code "230") (name "unconnected-(U14-D4B-PadL4)") (class "Default")
      (node (ref "U14") (pin "L4") (pinfunction "D4B_L4") (pintype "passive+no_connect"))
    )
    (net (code "231") (name "unconnected-(U14-D5B-PadM4)") (class "Default")
      (node (ref "U14") (pin "M4") (pinfunction "D5B_M4") (pintype "passive+no_connect"))
    )
    (net (code "232") (name "unconnected-(U14-D6B-PadN4)") (class "Default")
      (node (ref "U14") (pin "N4") (pinfunction "D6B_N4") (pintype "passive+no_connect"))
    )
    (net (code "233") (name "unconnected-(U14-HVout65-PadA2)") (class "Default")
      (node (ref "U14") (pin "A2") (pinfunction "HVout65_A2") (pintype "passive+no_connect"))
    )
    (net (code "234") (name "unconnected-(U14-HVout66-PadA1)") (class "Default")
      (node (ref "U14") (pin "A1") (pinfunction "HVout66_A1") (pintype "passive+no_connect"))
    )
    (net (code "235") (name "unconnected-(U14-HVout67-PadB1)") (class "Default")
      (node (ref "U14") (pin "B1") (pinfunction "HVout67_B1") (pintype "passive+no_connect"))
    )
    (net (code "236") (name "unconnected-(U14-HVout68-PadC2)") (class "Default")
      (node (ref "U14") (pin "C2") (pinfunction "HVout68_C2") (pintype "passive+no_connect"))
    )
    (net (code "237") (name "unconnected-(U14-HVout69-PadC1)") (class "Default")
      (node (ref "U14") (pin "C1") (pinfunction "HVout69_C1") (pintype "passive+no_connect"))
    )
    (net (code "238") (name "unconnected-(U14-HVout70-PadD3)") (class "Default")
      (node (ref "U14") (pin "D3") (pinfunction "HVout70_D3") (pintype "passive+no_connect"))
    )
    (net (code "239") (name "unconnected-(U14-HVout71-PadD2)") (class "Default")
      (node (ref "U14") (pin "D2") (pinfunction "HVout71_D2") (pintype "passive+no_connect"))
    )
    (net (code "240") (name "unconnected-(U14-HVout72-PadD1)") (class "Default")
      (node (ref "U14") (pin "D1") (pinfunction "HVout72_D1") (pintype "passive+no_connect"))
    )
    (net (code "241") (name "unconnected-(U14-HVout73-PadE3)") (class "Default")
      (node (ref "U14") (pin "E3") (pinfunction "HVout73_E3") (pintype "passive+no_connect"))
    )
    (net (code "242") (name "unconnected-(U14-HVout74-PadE2)") (class "Default")
      (node (ref "U14") (pin "E2") (pinfunction "HVout74_E2") (pintype "passive+no_connect"))
    )
    (net (code "243") (name "unconnected-(U14-HVout75-PadE1)") (class "Default")
      (node (ref "U14") (pin "E1") (pinfunction "HVout75_E1") (pintype "passive+no_connect"))
    )
    (net (code "244") (name "unconnected-(U14-HVout76-PadF3)") (class "Default")
      (node (ref "U14") (pin "F3") (pinfunction "HVout76_F3") (pintype "passive+no_connect"))
    )
    (net (code "245") (name "unconnected-(U14-HVout77-PadF2)") (class "Default")
      (node (ref "U14") (pin "F2") (pinfunction "HVout77_F2") (pintype "passive+no_connect"))
    )
    (net (code "246") (name "unconnected-(U14-HVout78-PadF1)") (class "Default")
      (node (ref "U14") (pin "F1") (pinfunction "HVout78_F1") (pintype "passive+no_connect"))
    )
    (net (code "247") (name "unconnected-(U14-HVout79-PadG3)") (class "Default")
      (node (ref "U14") (pin "G3") (pinfunction "HVout79_G3") (pintype "passive+no_connect"))
    )
    (net (code "248") (name "unconnected-(U14-HVout80-PadG2)") (class "Default")
      (node (ref "U14") (pin "G2") (pinfunction "HVout80_G2") (pintype "passive+no_connect"))
    )
    (net (code "249") (name "unconnected-(U14-HVout81-PadG1)") (class "Default")
      (node (ref "U14") (pin "G1") (pinfunction "HVout81_G1") (pintype "passive+no_connect"))
    )
    (net (code "250") (name "unconnected-(U14-HVout82-PadH3)") (class "Default")
      (node (ref "U14") (pin "H3") (pinfunction "HVout82_H3") (pintype "passive+no_connect"))
    )
    (net (code "251") (name "unconnected-(U14-HVout83-PadH2)") (class "Default")
      (node (ref "U14") (pin "H2") (pinfunction "HVout83_H2") (pintype "passive+no_connect"))
    )
    (net (code "252") (name "unconnected-(U14-HVout84-PadH1)") (class "Default")
      (node (ref "U14") (pin "H1") (pinfunction "HVout84_H1") (pintype "passive+no_connect"))
    )
    (net (code "253") (name "unconnected-(U14-HVout85-PadJ3)") (class "Default")
      (node (ref "U14") (pin "J3") (pinfunction "HVout85_J3") (pintype "passive+no_connect"))
    )
    (net (code "254") (name "unconnected-(U14-HVout86-PadJ2)") (class "Default")
      (node (ref "U14") (pin "J2") (pinfunction "HVout86_J2") (pintype "passive+no_connect"))
    )
    (net (code "255") (name "unconnected-(U14-HVout87-PadJ1)") (class "Default")
      (node (ref "U14") (pin "J1") (pinfunction "HVout87_J1") (pintype "passive+no_connect"))
    )
    (net (code "256") (name "unconnected-(U14-HVout88-PadK3)") (class "Default")
      (node (ref "U14") (pin "K3") (pinfunction "HVout88_K3") (pintype "passive+no_connect"))
    )
    (net (code "257") (name "unconnected-(U14-HVout89-PadK2)") (class "Default")
      (node (ref "U14") (pin "K2") (pinfunction "HVout89_K2") (pintype "passive+no_connect"))
    )
    (net (code "258") (name "unconnected-(U14-HVout90-PadK1)") (class "Default")
      (node (ref "U14") (pin "K1") (pinfunction "HVout90_K1") (pintype "passive+no_connect"))
    )
    (net (code "259") (name "unconnected-(U14-HVout91-PadL2)") (class "Default")
      (node (ref "U14") (pin "L2") (pinfunction "HVout91_L2") (pintype "passive+no_connect"))
    )
    (net (code "260") (name "unconnected-(U14-HVout92-PadL1)") (class "Default")
      (node (ref "U14") (pin "L1") (pinfunction "HVout92_L1") (pintype "passive+no_connect"))
    )
    (net (code "261") (name "unconnected-(U14-HVout93-PadM1)") (class "Default")
      (node (ref "U14") (pin "M1") (pinfunction "HVout93_M1") (pintype "passive+no_connect"))
    )
    (net (code "262") (name "unconnected-(U14-HVout94-PadN1)") (class "Default")
      (node (ref "U14") (pin "N1") (pinfunction "HVout94_N1") (pintype "passive+no_connect"))
    )
    (net (code "263") (name "unconnected-(U14-HVout95-PadM2)") (class "Default")
      (node (ref "U14") (pin "M2") (pinfunction "HVout95_M2") (pintype "passive+no_connect"))
    )
    (net (code "264") (name "unconnected-(U14-HVout96-PadN2)") (class "Default")
      (node (ref "U14") (pin "N2") (pinfunction "HVout96_N2") (pintype "passive+no_connect"))
    )
    (net (code "265") (name "unconnected-(U14-NC-PadD4)") (class "Default")
      (node (ref "U14") (pin "D4") (pinfunction "NC_D4") (pintype "passive+no_connect"))
    )
    (net (code "266") (name "unconnected-(U14-NC-PadD5)") (class "Default")
      (node (ref "U14") (pin "D5") (pinfunction "NC_D5") (pintype "passive+no_connect"))
    )
    (net (code "267") (name "unconnected-(U14-NC-PadD6)") (class "Default")
      (node (ref "U14") (pin "D6") (pinfunction "NC_D6") (pintype "passive+no_connect"))
    )
    (net (code "268") (name "unconnected-(U14-NC-PadD7)") (class "Default")
      (node (ref "U14") (pin "D7") (pinfunction "NC_D7") (pintype "passive+no_connect"))
    )
    (net (code "269") (name "unconnected-(U14-NC-PadD8)") (class "Default")
      (node (ref "U14") (pin "D8") (pinfunction "NC_D8") (pintype "passive+no_connect"))
    )
    (net (code "270") (name "unconnected-(U14-NC-PadD9)") (class "Default")
      (node (ref "U14") (pin "D9") (pinfunction "NC_D9") (pintype "passive+no_connect"))
    )
    (net (code "271") (name "unconnected-(U14-NC-PadD10)") (class "Default")
      (node (ref "U14") (pin "D10") (pinfunction "NC_D10") (pintype "passive+no_connect"))
    )
    (net (code "272") (name "unconnected-(U14-NC-PadE4)") (class "Default")
      (node (ref "U14") (pin "E4") (pinfunction "NC_E4") (pintype "passive+no_connect"))
    )
    (net (code "273") (name "unconnected-(U14-NC-PadE7)") (class "Default")
      (node (ref "U14") (pin "E7") (pinfunction "NC_E7") (pintype "passive+no_connect"))
    )
    (net (code "274") (name "unconnected-(U14-NC-PadE10)") (class "Default")
      (node (ref "U14") (pin "E10") (pinfunction "NC_E10") (pintype "passive+no_connect"))
    )
    (net (code "275") (name "unconnected-(U14-NC-PadF4)") (class "Default")
      (node (ref "U14") (pin "F4") (pinfunction "NC_F4") (pintype "passive+no_connect"))
    )
    (net (code "276") (name "unconnected-(U14-NC-PadF10)") (class "Default")
      (node (ref "U14") (pin "F10") (pinfunction "NC_F10") (pintype "passive+no_connect"))
    )
    (net (code "277") (name "unconnected-(U14-NC-PadG4)") (class "Default")
      (node (ref "U14") (pin "G4") (pinfunction "NC_G4") (pintype "passive+no_connect"))
    )
    (net (code "278") (name "unconnected-(U14-NC-PadG10)") (class "Default")
      (node (ref "U14") (pin "G10") (pinfunction "NC_G10") (pintype "passive+no_connect"))
    )
    (net (code "279") (name "unconnected-(U14-NC-PadH4)") (class "Default")
      (node (ref "U14") (pin "H4") (pinfunction "NC_H4") (pintype "passive+no_connect"))
    )
    (net (code "280") (name "unconnected-(U14-NC-PadH10)") (class "Default")
      (node (ref "U14") (pin "H10") (pinfunction "NC_H10") (pintype "passive+no_connect"))
    )
    (net (code "281") (name "unconnected-(U14-NC-PadJ4)") (class "Default")
      (node (ref "U14") (pin "J4") (pinfunction "NC_J4") (pintype "passive+no_connect"))
    )
    (net (code "282") (name "unconnected-(U14-NC-PadJ10)") (class "Default")
      (node (ref "U14") (pin "J10") (pinfunction "NC_J10") (pintype "passive+no_connect"))
    )
    (net (code "283") (name "unconnected-(U14-NC-PadK4)") (class "Default")
      (node (ref "U14") (pin "K4") (pinfunction "NC_K4") (pintype "passive+no_connect"))
    )
    (net (code "284") (name "unconnected-(U14-NC-PadK9)") (class "Default")
      (node (ref "U14") (pin "K9") (pinfunction "NC_K9") (pintype "passive+no_connect"))
    )
    (net (code "285") (name "unconnected-(U14-NC-PadK10)") (class "Default")
      (node (ref "U14") (pin "K10") (pinfunction "NC_K10") (pintype "passive+no_connect"))
    )
    (net (code "286") (name "unconnected-(U14-NC-PadL3)") (class "Default")
      (node (ref "U14") (pin "L3") (pinfunction "NC_L3") (pintype "passive+no_connect"))
    )
    (net (code "287") (name "unconnected-(U14-NC-PadL10)") (class "Default")
      (node (ref "U14") (pin "L10") (pinfunction "NC_L10") (pintype "passive+no_connect"))
    )
    (net (code "288") (name "unconnected-(U14-NC-PadM3)") (class "Default")
      (node (ref "U14") (pin "M3") (pinfunction "NC_M3") (pintype "passive+no_connect"))
    )
    (net (code "289") (name "unconnected-(U14-NC-PadN3)") (class "Default")
      (node (ref "U14") (pin "N3") (pinfunction "NC_N3") (pintype "passive+no_connect"))
    )
  )
)
